# driver_board_v2.net
KiCad netlist of a schematic drawn in EAGLE
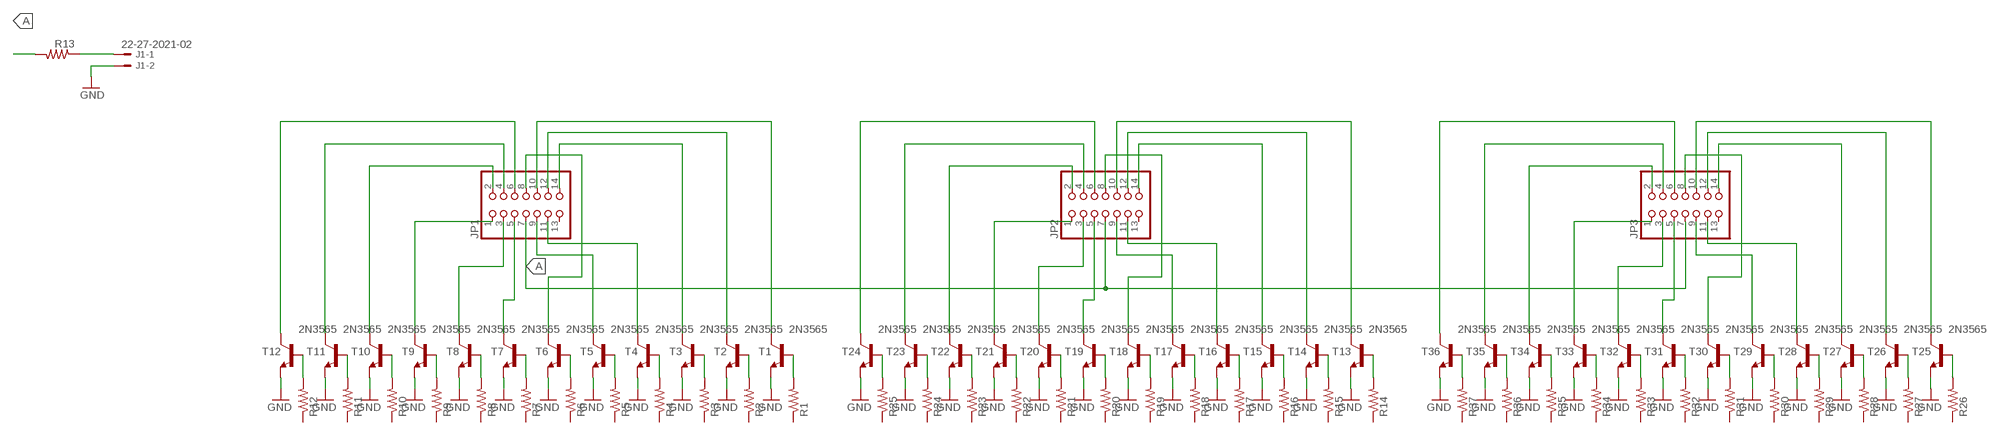
[diagram p0: schematic, sheet 1]

(export (version "E")
  (design (tool "Eeschema 10.0.6"))
  (components
    (comp (ref "J1")
      (value "22-27-2021-02")
      (footprint "eagle-import:6410-02")
      (libsource (lib "eagle-import") (part "22-?-0227-2021"))
    )
    (comp (ref "JP1")
      (value "PINHD-2X7")
      (footprint "eagle-import:2X07")
      (libsource (lib "eagle-import") (part "PINHD-2X7"))
    )
    (comp (ref "JP2")
      (value "PINHD-2X7")
      (footprint "eagle-import:2X07")
      (libsource (lib "eagle-import") (part "PINHD-2X7"))
    )
    (comp (ref "JP3")
      (value "PINHD-2X7")
      (footprint "eagle-import:2X07")
      (libsource (lib "eagle-import") (part "PINHD-2X7"))
    )
    (comp (ref "R1")
      (value "R-US_0204/7")
      (footprint "eagle-import:0204_7")
      (libsource (lib "eagle-import") (part "R-US_0204/7"))
    )
    (comp (ref "R2")
      (value "R-US_0204/7")
      (footprint "eagle-import:0204_7")
      (libsource (lib "eagle-import") (part "R-US_0204/7"))
    )
    (comp (ref "R3")
      (value "R-US_0204/7")
      (footprint "eagle-import:0204_7")
      (libsource (lib "eagle-import") (part "R-US_0204/7"))
    )
    (comp (ref "R4")
      (value "R-US_0204/7")
      (footprint "eagle-import:0204_7")
      (libsource (lib "eagle-import") (part "R-US_0204/7"))
    )
    (comp (ref "R5")
      (value "R-US_0204/7")
      (footprint "eagle-import:0204_7")
      (libsource (lib "eagle-import") (part "R-US_0204/7"))
    )
    (comp (ref "R6")
      (value "R-US_0204/7")
      (footprint "eagle-import:0204_7")
      (libsource (lib "eagle-import") (part "R-US_0204/7"))
    )
    (comp (ref "R7")
      (value "R-US_0204/7")
      (footprint "eagle-import:0204_7")
      (libsource (lib "eagle-import") (part "R-US_0204/7"))
    )
    (comp (ref "R8")
      (value "R-US_0204/7")
      (footprint "eagle-import:0204_7")
      (libsource (lib "eagle-import") (part "R-US_0204/7"))
    )
    (comp (ref "R9")
      (value "R-US_0204/7")
      (footprint "eagle-import:0204_7")
      (libsource (lib "eagle-import") (part "R-US_0204/7"))
    )
    (comp (ref "R10")
      (value "R-US_0204/7")
      (footprint "eagle-import:0204_7")
      (libsource (lib "eagle-import") (part "R-US_0204/7"))
    )
    (comp (ref "R11")
      (value "R-US_0204/7")
      (footprint "eagle-import:0204_7")
      (libsource (lib "eagle-import") (part "R-US_0204/7"))
    )
    (comp (ref "R12")
      (value "R-US_0204/7")
      (footprint "eagle-import:0204_7")
      (libsource (lib "eagle-import") (part "R-US_0204/7"))
    )
    (comp (ref "R13")
      (value "R-US_0204/7")
      (footprint "eagle-import:0204_7")
      (libsource (lib "eagle-import") (part "R-US_0204/7"))
    )
    (comp (ref "R14")
      (value "R-US_0204/7")
      (footprint "eagle-import:0204_7")
      (libsource (lib "eagle-import") (part "R-US_0204/7"))
    )
    (comp (ref "R15")
      (value "R-US_0204/7")
      (footprint "eagle-import:0204_7")
      (libsource (lib "eagle-import") (part "R-US_0204/7"))
    )
    (comp (ref "R16")
      (value "R-US_0204/7")
      (footprint "eagle-import:0204_7")
      (libsource (lib "eagle-import") (part "R-US_0204/7"))
    )
    (comp (ref "R17")
      (value "R-US_0204/7")
      (footprint "eagle-import:0204_7")
      (libsource (lib "eagle-import") (part "R-US_0204/7"))
    )
    (comp (ref "R18")
      (value "R-US_0204/7")
      (footprint "eagle-import:0204_7")
      (libsource (lib "eagle-import") (part "R-US_0204/7"))
    )
    (comp (ref "R19")
      (value "R-US_0204/7")
      (footprint "eagle-import:0204_7")
      (libsource (lib "eagle-import") (part "R-US_0204/7"))
    )
    (comp (ref "R20")
      (value "R-US_0204/7")
      (footprint "eagle-import:0204_7")
      (libsource (lib "eagle-import") (part "R-US_0204/7"))
    )
    (comp (ref "R21")
      (value "R-US_0204/7")
      (footprint "eagle-import:0204_7")
      (libsource (lib "eagle-import") (part "R-US_0204/7"))
    )
    (comp (ref "R22")
      (value "R-US_0204/7")
      (footprint "eagle-import:0204_7")
      (libsource (lib "eagle-import") (part "R-US_0204/7"))
    )
    (comp (ref "R23")
      (value "R-US_0204/7")
      (footprint "eagle-import:0204_7")
      (libsource (lib "eagle-import") (part "R-US_0204/7"))
    )
    (comp (ref "R24")
      (value "R-US_0204/7")
      (footprint "eagle-import:0204_7")
      (libsource (lib "eagle-import") (part "R-US_0204/7"))
    )
    (comp (ref "R25")
      (value "R-US_0204/7")
      (footprint "eagle-import:0204_7")
      (libsource (lib "eagle-import") (part "R-US_0204/7"))
    )
    (comp (ref "R26")
      (value "R-US_0204/7")
      (footprint "eagle-import:0204_7")
      (libsource (lib "eagle-import") (part "R-US_0204/7"))
    )
    (comp (ref "R27")
      (value "R-US_0204/7")
      (footprint "eagle-import:0204_7")
      (libsource (lib "eagle-import") (part "R-US_0204/7"))
    )
    (comp (ref "R28")
      (value "R-US_0204/7")
      (footprint "eagle-import:0204_7")
      (libsource (lib "eagle-import") (part "R-US_0204/7"))
    )
    (comp (ref "R29")
      (value "R-US_0204/7")
      (footprint "eagle-import:0204_7")
      (libsource (lib "eagle-import") (part "R-US_0204/7"))
    )
    (comp (ref "R30")
      (value "R-US_0204/7")
      (footprint "eagle-import:0204_7")
      (libsource (lib "eagle-import") (part "R-US_0204/7"))
    )
    (comp (ref "R31")
      (value "R-US_0204/7")
      (footprint "eagle-import:0204_7")
      (libsource (lib "eagle-import") (part "R-US_0204/7"))
    )
    (comp (ref "R32")
      (value "R-US_0204/7")
      (footprint "eagle-import:0204_7")
      (libsource (lib "eagle-import") (part "R-US_0204/7"))
    )
    (comp (ref "R33")
      (value "R-US_0204/7")
      (footprint "eagle-import:0204_7")
      (libsource (lib "eagle-import") (part "R-US_0204/7"))
    )
    (comp (ref "R34")
      (value "R-US_0204/7")
      (footprint "eagle-import:0204_7")
      (libsource (lib "eagle-import") (part "R-US_0204/7"))
    )
    (comp (ref "R35")
      (value "R-US_0204/7")
      (footprint "eagle-import:0204_7")
      (libsource (lib "eagle-import") (part "R-US_0204/7"))
    )
    (comp (ref "R36")
      (value "R-US_0204/7")
      (footprint "eagle-import:0204_7")
      (libsource (lib "eagle-import") (part "R-US_0204/7"))
    )
    (comp (ref "R37")
      (value "R-US_0204/7")
      (footprint "eagle-import:0204_7")
      (libsource (lib "eagle-import") (part "R-US_0204/7"))
    )
    (comp (ref "T1")
      (value "2N3565")
      (footprint "eagle-import:TO92")
      (libsource (lib "eagle-import") (part "2N3565"))
    )
    (comp (ref "T2")
      (value "2N3565")
      (footprint "eagle-import:TO92")
      (libsource (lib "eagle-import") (part "2N3565"))
    )
    (comp (ref "T3")
      (value "2N3565")
      (footprint "eagle-import:TO92")
      (libsource (lib "eagle-import") (part "2N3565"))
    )
    (comp (ref "T4")
      (value "2N3565")
      (footprint "eagle-import:TO92")
      (libsource (lib "eagle-import") (part "2N3565"))
    )
    (comp (ref "T5")
      (value "2N3565")
      (footprint "eagle-import:TO92")
      (libsource (lib "eagle-import") (part "2N3565"))
    )
    (comp (ref "T6")
      (value "2N3565")
      (footprint "eagle-import:TO92")
      (libsource (lib "eagle-import") (part "2N3565"))
    )
    (comp (ref "T7")
      (value "2N3565")
      (footprint "eagle-import:TO92")
      (libsource (lib "eagle-import") (part "2N3565"))
    )
    (comp (ref "T8")
      (value "2N3565")
      (footprint "eagle-import:TO92")
      (libsource (lib "eagle-import") (part "2N3565"))
    )
    (comp (ref "T9")
      (value "2N3565")
      (footprint "eagle-import:TO92")
      (libsource (lib "eagle-import") (part "2N3565"))
    )
    (comp (ref "T10")
      (value "2N3565")
      (footprint "eagle-import:TO92")
      (libsource (lib "eagle-import") (part "2N3565"))
    )
    (comp (ref "T11")
      (value "2N3565")
      (footprint "eagle-import:TO92")
      (libsource (lib "eagle-import") (part "2N3565"))
    )
    (comp (ref "T12")
      (value "2N3565")
      (footprint "eagle-import:TO92")
      (libsource (lib "eagle-import") (part "2N3565"))
    )
    (comp (ref "T13")
      (value "2N3565")
      (footprint "eagle-import:TO92")
      (libsource (lib "eagle-import") (part "2N3565"))
    )
    (comp (ref "T14")
      (value "2N3565")
      (footprint "eagle-import:TO92")
      (libsource (lib "eagle-import") (part "2N3565"))
    )
    (comp (ref "T15")
      (value "2N3565")
      (footprint "eagle-import:TO92")
      (libsource (lib "eagle-import") (part "2N3565"))
    )
    (comp (ref "T16")
      (value "2N3565")
      (footprint "eagle-import:TO92")
      (libsource (lib "eagle-import") (part "2N3565"))
    )
    (comp (ref "T17")
      (value "2N3565")
      (footprint "eagle-import:TO92")
      (libsource (lib "eagle-import") (part "2N3565"))
    )
    (comp (ref "T18")
      (value "2N3565")
      (footprint "eagle-import:TO92")
      (libsource (lib "eagle-import") (part "2N3565"))
    )
    (comp (ref "T19")
      (value "2N3565")
      (footprint "eagle-import:TO92")
      (libsource (lib "eagle-import") (part "2N3565"))
    )
    (comp (ref "T20")
      (value "2N3565")
      (footprint "eagle-import:TO92")
      (libsource (lib "eagle-import") (part "2N3565"))
    )
    (comp (ref "T21")
      (value "2N3565")
      (footprint "eagle-import:TO92")
      (libsource (lib "eagle-import") (part "2N3565"))
    )
    (comp (ref "T22")
      (value "2N3565")
      (footprint "eagle-import:TO92")
      (libsource (lib "eagle-import") (part "2N3565"))
    )
    (comp (ref "T23")
      (value "2N3565")
      (footprint "eagle-import:TO92")
      (libsource (lib "eagle-import") (part "2N3565"))
    )
    (comp (ref "T24")
      (value "2N3565")
      (footprint "eagle-import:TO92")
      (libsource (lib "eagle-import") (part "2N3565"))
    )
    (comp (ref "T25")
      (value "2N3565")
      (footprint "eagle-import:TO92")
      (libsource (lib "eagle-import") (part "2N3565"))
    )
    (comp (ref "T26")
      (value "2N3565")
      (footprint "eagle-import:TO92")
      (libsource (lib "eagle-import") (part "2N3565"))
    )
    (comp (ref "T27")
      (value "2N3565")
      (footprint "eagle-import:TO92")
      (libsource (lib "eagle-import") (part "2N3565"))
    )
    (comp (ref "T28")
      (value "2N3565")
      (footprint "eagle-import:TO92")
      (libsource (lib "eagle-import") (part "2N3565"))
    )
    (comp (ref "T29")
      (value "2N3565")
      (footprint "eagle-import:TO92")
      (libsource (lib "eagle-import") (part "2N3565"))
    )
    (comp (ref "T30")
      (value "2N3565")
      (footprint "eagle-import:TO92")
      (libsource (lib "eagle-import") (part "2N3565"))
    )
    (comp (ref "T31")
      (value "2N3565")
      (footprint "eagle-import:TO92")
      (libsource (lib "eagle-import") (part "2N3565"))
    )
    (comp (ref "T32")
      (value "2N3565")
      (footprint "eagle-import:TO92")
      (libsource (lib "eagle-import") (part "2N3565"))
    )
    (comp (ref "T33")
      (value "2N3565")
      (footprint "eagle-import:TO92")
      (libsource (lib "eagle-import") (part "2N3565"))
    )
    (comp (ref "T34")
      (value "2N3565")
      (footprint "eagle-import:TO92")
      (libsource (lib "eagle-import") (part "2N3565"))
    )
    (comp (ref "T35")
      (value "2N3565")
      (footprint "eagle-import:TO92")
      (libsource (lib "eagle-import") (part "2N3565"))
    )
    (comp (ref "T36")
      (value "2N3565")
      (footprint "eagle-import:TO92")
      (libsource (lib "eagle-import") (part "2N3565"))
    )
  )
  (nets
    (net (code "1") (name "A") (class "Default")
      (node (ref "JP1") (pin "7") (pinfunction "7_7") (pintype "passive"))
      (node (ref "JP2") (pin "7") (pinfunction "7_7") (pintype "passive"))
      (node (ref "JP3") (pin "7") (pinfunction "7_7") (pintype "passive"))
      (node (ref "R13") (pin "2") (pinfunction "2_2") (pintype "passive"))
    )
    (net (code "2") (name "GND") (class "Default")
      (node (ref "J1") (pin "2") (pinfunction "S_2") (pintype "passive"))
      (node (ref "T1") (pin "3") (pinfunction "E_3") (pintype "passive"))
      (node (ref "T10") (pin "3") (pinfunction "E_3") (pintype "passive"))
      (node (ref "T11") (pin "3") (pinfunction "E_3") (pintype "passive"))
      (node (ref "T12") (pin "3") (pinfunction "E_3") (pintype "passive"))
      (node (ref "T13") (pin "3") (pinfunction "E_3") (pintype "passive"))
      (node (ref "T14") (pin "3") (pinfunction "E_3") (pintype "passive"))
      (node (ref "T15") (pin "3") (pinfunction "E_3") (pintype "passive"))
      (node (ref "T16") (pin "3") (pinfunction "E_3") (pintype "passive"))
      (node (ref "T17") (pin "3") (pinfunction "E_3") (pintype "passive"))
      (node (ref "T18") (pin "3") (pinfunction "E_3") (pintype "passive"))
      (node (ref "T19") (pin "3") (pinfunction "E_3") (pintype "passive"))
      (node (ref "T2") (pin "3") (pinfunction "E_3") (pintype "passive"))
      (node (ref "T20") (pin "3") (pinfunction "E_3") (pintype "passive"))
      (node (ref "T21") (pin "3") (pinfunction "E_3") (pintype "passive"))
      (node (ref "T22") (pin "3") (pinfunction "E_3") (pintype "passive"))
      (node (ref "T23") (pin "3") (pinfunction "E_3") (pintype "passive"))
      (node (ref "T24") (pin "3") (pinfunction "E_3") (pintype "passive"))
      (node (ref "T25") (pin "3") (pinfunction "E_3") (pintype "passive"))
      (node (ref "T26") (pin "3") (pinfunction "E_3") (pintype "passive"))
      (node (ref "T27") (pin "3") (pinfunction "E_3") (pintype "passive"))
      (node (ref "T28") (pin "3") (pinfunction "E_3") (pintype "passive"))
      (node (ref "T29") (pin "3") (pinfunction "E_3") (pintype "passive"))
      (node (ref "T3") (pin "3") (pinfunction "E_3") (pintype "passive"))
      (node (ref "T30") (pin "3") (pinfunction "E_3") (pintype "passive"))
      (node (ref "T31") (pin "3") (pinfunction "E_3") (pintype "passive"))
      (node (ref "T32") (pin "3") (pinfunction "E_3") (pintype "passive"))
      (node (ref "T33") (pin "3") (pinfunction "E_3") (pintype "passive"))
      (node (ref "T34") (pin "3") (pinfunction "E_3") (pintype "passive"))
      (node (ref "T35") (pin "3") (pinfunction "E_3") (pintype "passive"))
      (node (ref "T36") (pin "3") (pinfunction "E_3") (pintype "passive"))
      (node (ref "T4") (pin "3") (pinfunction "E_3") (pintype "passive"))
      (node (ref "T5") (pin "3") (pinfunction "E_3") (pintype "passive"))
      (node (ref "T6") (pin "3") (pinfunction "E_3") (pintype "passive"))
      (node (ref "T7") (pin "3") (pinfunction "E_3") (pintype "passive"))
      (node (ref "T8") (pin "3") (pinfunction "E_3") (pintype "passive"))
      (node (ref "T9") (pin "3") (pinfunction "E_3") (pintype "passive"))
    )
    (net (code "3") (name "Net-(J1A-S)") (class "Default")
      (node (ref "J1") (pin "1") (pinfunction "S_1") (pintype "passive"))
      (node (ref "R13") (pin "1") (pinfunction "1_1") (pintype "passive"))
    )
    (net (code "4") (name "Net-(T1-B)") (class "Default")
      (node (ref "R1") (pin "2") (pinfunction "2_2") (pintype "passive"))
      (node (ref "T1") (pin "2") (pinfunction "B_2") (pintype "passive"))
    )
    (net (code "5") (name "Net-(T1-C)") (class "Default")
      (node (ref "JP1") (pin "10") (pinfunction "10_10") (pintype "passive"))
      (node (ref "T1") (pin "1") (pinfunction "C_1") (pintype "passive"))
    )
    (net (code "6") (name "Net-(T2-B)") (class "Default")
      (node (ref "R2") (pin "2") (pinfunction "2_2") (pintype "passive"))
      (node (ref "T2") (pin "2") (pinfunction "B_2") (pintype "passive"))
    )
    (net (code "7") (name "Net-(T2-C)") (class "Default")
      (node (ref "JP1") (pin "12") (pinfunction "12_12") (pintype "passive"))
      (node (ref "T2") (pin "1") (pinfunction "C_1") (pintype "passive"))
    )
    (net (code "8") (name "Net-(T3-B)") (class "Default")
      (node (ref "R3") (pin "2") (pinfunction "2_2") (pintype "passive"))
      (node (ref "T3") (pin "2") (pinfunction "B_2") (pintype "passive"))
    )
    (net (code "9") (name "Net-(T3-C)") (class "Default")
      (node (ref "JP1") (pin "14") (pinfunction "14_14") (pintype "passive"))
      (node (ref "T3") (pin "1") (pinfunction "C_1") (pintype "passive"))
    )
    (net (code "10") (name "Net-(T4-B)") (class "Default")
      (node (ref "R4") (pin "2") (pinfunction "2_2") (pintype "passive"))
      (node (ref "T4") (pin "2") (pinfunction "B_2") (pintype "passive"))
    )
    (net (code "11") (name "Net-(T4-C)") (class "Default")
      (node (ref "JP1") (pin "11") (pinfunction "11_11") (pintype "passive"))
      (node (ref "T4") (pin "1") (pinfunction "C_1") (pintype "passive"))
    )
    (net (code "12") (name "Net-(T5-B)") (class "Default")
      (node (ref "R5") (pin "2") (pinfunction "2_2") (pintype "passive"))
      (node (ref "T5") (pin "2") (pinfunction "B_2") (pintype "passive"))
    )
    (net (code "13") (name "Net-(T5-C)") (class "Default")
      (node (ref "JP1") (pin "9") (pinfunction "9_9") (pintype "passive"))
      (node (ref "T5") (pin "1") (pinfunction "C_1") (pintype "passive"))
    )
    (net (code "14") (name "Net-(T6-B)") (class "Default")
      (node (ref "R6") (pin "2") (pinfunction "2_2") (pintype "passive"))
      (node (ref "T6") (pin "2") (pinfunction "B_2") (pintype "passive"))
    )
    (net (code "15") (name "Net-(T6-C)") (class "Default")
      (node (ref "JP1") (pin "8") (pinfunction "8_8") (pintype "passive"))
      (node (ref "T6") (pin "1") (pinfunction "C_1") (pintype "passive"))
    )
    (net (code "16") (name "Net-(T7-B)") (class "Default")
      (node (ref "R7") (pin "2") (pinfunction "2_2") (pintype "passive"))
      (node (ref "T7") (pin "2") (pinfunction "B_2") (pintype "passive"))
    )
    (net (code "17") (name "Net-(T7-C)") (class "Default")
      (node (ref "JP1") (pin "5") (pinfunction "5_5") (pintype "passive"))
      (node (ref "T7") (pin "1") (pinfunction "C_1") (pintype "passive"))
    )
    (net (code "18") (name "Net-(T8-B)") (class "Default")
      (node (ref "R8") (pin "2") (pinfunction "2_2") (pintype "passive"))
      (node (ref "T8") (pin "2") (pinfunction "B_2") (pintype "passive"))
    )
    (net (code "19") (name "Net-(T8-C)") (class "Default")
      (node (ref "JP1") (pin "3") (pinfunction "3_3") (pintype "passive"))
      (node (ref "T8") (pin "1") (pinfunction "C_1") (pintype "passive"))
    )
    (net (code "20") (name "Net-(T9-B)") (class "Default")
      (node (ref "R9") (pin "2") (pinfunction "2_2") (pintype "passive"))
      (node (ref "T9") (pin "2") (pinfunction "B_2") (pintype "passive"))
    )
    (net (code "21") (name "Net-(T9-C)") (class "Default")
      (node (ref "JP1") (pin "1") (pinfunction "1_1") (pintype "passive"))
      (node (ref "T9") (pin "1") (pinfunction "C_1") (pintype "passive"))
    )
    (net (code "22") (name "Net-(T10-B)") (class "Default")
      (node (ref "R10") (pin "2") (pinfunction "2_2") (pintype "passive"))
      (node (ref "T10") (pin "2") (pinfunction "B_2") (pintype "passive"))
    )
    (net (code "23") (name "Net-(T10-C)") (class "Default")
      (node (ref "JP1") (pin "2") (pinfunction "2_2") (pintype "passive"))
      (node (ref "T10") (pin "1") (pinfunction "C_1") (pintype "passive"))
    )
    (net (code "24") (name "Net-(T11-B)") (class "Default")
      (node (ref "R11") (pin "2") (pinfunction "2_2") (pintype "passive"))
      (node (ref "T11") (pin "2") (pinfunction "B_2") (pintype "passive"))
    )
    (net (code "25") (name "Net-(T11-C)") (class "Default")
      (node (ref "JP1") (pin "4") (pinfunction "4_4") (pintype "passive"))
      (node (ref "T11") (pin "1") (pinfunction "C_1") (pintype "passive"))
    )
    (net (code "26") (name "Net-(T12-B)") (class "Default")
      (node (ref "R12") (pin "2") (pinfunction "2_2") (pintype "passive"))
      (node (ref "T12") (pin "2") (pinfunction "B_2") (pintype "passive"))
    )
    (net (code "27") (name "Net-(T12-C)") (class "Default")
      (node (ref "JP1") (pin "6") (pinfunction "6_6") (pintype "passive"))
      (node (ref "T12") (pin "1") (pinfunction "C_1") (pintype "passive"))
    )
    (net (code "28") (name "Net-(T13-B)") (class "Default")
      (node (ref "R14") (pin "2") (pinfunction "2_2") (pintype "passive"))
      (node (ref "T13") (pin "2") (pinfunction "B_2") (pintype "passive"))
    )
    (net (code "29") (name "Net-(T13-C)") (class "Default")
      (node (ref "JP2") (pin "10") (pinfunction "10_10") (pintype "passive"))
      (node (ref "T13") (pin "1") (pinfunction "C_1") (pintype "passive"))
    )
    (net (code "30") (name "Net-(T14-B)") (class "Default")
      (node (ref "R15") (pin "2") (pinfunction "2_2") (pintype "passive"))
      (node (ref "T14") (pin "2") (pinfunction "B_2") (pintype "passive"))
    )
    (net (code "31") (name "Net-(T14-C)") (class "Default")
      (node (ref "JP2") (pin "12") (pinfunction "12_12") (pintype "passive"))
      (node (ref "T14") (pin "1") (pinfunction "C_1") (pintype "passive"))
    )
    (net (code "32") (name "Net-(T15-B)") (class "Default")
      (node (ref "R16") (pin "2") (pinfunction "2_2") (pintype "passive"))
      (node (ref "T15") (pin "2") (pinfunction "B_2") (pintype "passive"))
    )
    (net (code "33") (name "Net-(T15-C)") (class "Default")
      (node (ref "JP2") (pin "14") (pinfunction "14_14") (pintype "passive"))
      (node (ref "T15") (pin "1") (pinfunction "C_1") (pintype "passive"))
    )
    (net (code "34") (name "Net-(T16-B)") (class "Default")
      (node (ref "R17") (pin "2") (pinfunction "2_2") (pintype "passive"))
      (node (ref "T16") (pin "2") (pinfunction "B_2") (pintype "passive"))
    )
    (net (code "35") (name "Net-(T16-C)") (class "Default")
      (node (ref "JP2") (pin "11") (pinfunction "11_11") (pintype "passive"))
      (node (ref "T16") (pin "1") (pinfunction "C_1") (pintype "passive"))
    )
    (net (code "36") (name "Net-(T17-B)") (class "Default")
      (node (ref "R18") (pin "2") (pinfunction "2_2") (pintype "passive"))
      (node (ref "T17") (pin "2") (pinfunction "B_2") (pintype "passive"))
    )
    (net (code "37") (name "Net-(T17-C)") (class "Default")
      (node (ref "JP2") (pin "9") (pinfunction "9_9") (pintype "passive"))
      (node (ref "T17") (pin "1") (pinfunction "C_1") (pintype "passive"))
    )
    (net (code "38") (name "Net-(T18-B)") (class "Default")
      (node (ref "R19") (pin "2") (pinfunction "2_2") (pintype "passive"))
      (node (ref "T18") (pin "2") (pinfunction "B_2") (pintype "passive"))
    )
    (net (code "39") (name "Net-(T18-C)") (class "Default")
      (node (ref "JP2") (pin "8") (pinfunction "8_8") (pintype "passive"))
      (node (ref "T18") (pin "1") (pinfunction "C_1") (pintype "passive"))
    )
    (net (code "40") (name "Net-(T19-B)") (class "Default")
      (node (ref "R20") (pin "2") (pinfunction "2_2") (pintype "passive"))
      (node (ref "T19") (pin "2") (pinfunction "B_2") (pintype "passive"))
    )
    (net (code "41") (name "Net-(T19-C)") (class "Default")
      (node (ref "JP2") (pin "5") (pinfunction "5_5") (pintype "passive"))
      (node (ref "T19") (pin "1") (pinfunction "C_1") (pintype "passive"))
    )
    (net (code "42") (name "Net-(T20-B)") (class "Default")
      (node (ref "R21") (pin "2") (pinfunction "2_2") (pintype "passive"))
      (node (ref "T20") (pin "2") (pinfunction "B_2") (pintype "passive"))
    )
    (net (code "43") (name "Net-(T20-C)") (class "Default")
      (node (ref "JP2") (pin "3") (pinfunction "3_3") (pintype "passive"))
      (node (ref "T20") (pin "1") (pinfunction "C_1") (pintype "passive"))
    )
    (net (code "44") (name "Net-(T21-B)") (class "Default")
      (node (ref "R22") (pin "2") (pinfunction "2_2") (pintype "passive"))
      (node (ref "T21") (pin "2") (pinfunction "B_2") (pintype "passive"))
    )
    (net (code "45") (name "Net-(T21-C)") (class "Default")
      (node (ref "JP2") (pin "1") (pinfunction "1_1") (pintype "passive"))
      (node (ref "T21") (pin "1") (pinfunction "C_1") (pintype "passive"))
    )
    (net (code "46") (name "Net-(T22-B)") (class "Default")
      (node (ref "R23") (pin "2") (pinfunction "2_2") (pintype "passive"))
      (node (ref "T22") (pin "2") (pinfunction "B_2") (pintype "passive"))
    )
    (net (code "47") (name "Net-(T22-C)") (class "Default")
      (node (ref "JP2") (pin "2") (pinfunction "2_2") (pintype "passive"))
      (node (ref "T22") (pin "1") (pinfunction "C_1") (pintype "passive"))
    )
    (net (code "48") (name "Net-(T23-B)") (class "Default")
      (node (ref "R24") (pin "2") (pinfunction "2_2") (pintype "passive"))
      (node (ref "T23") (pin "2") (pinfunction "B_2") (pintype "passive"))
    )
    (net (code "49") (name "Net-(T23-C)") (class "Default")
      (node (ref "JP2") (pin "4") (pinfunction "4_4") (pintype "passive"))
      (node (ref "T23") (pin "1") (pinfunction "C_1") (pintype "passive"))
    )
    (net (code "50") (name "Net-(T24-B)") (class "Default")
      (node (ref "R25") (pin "2") (pinfunction "2_2") (pintype "passive"))
      (node (ref "T24") (pin "2") (pinfunction "B_2") (pintype "passive"))
    )
    (net (code "51") (name "Net-(T24-C)") (class "Default")
      (node (ref "JP2") (pin "6") (pinfunction "6_6") (pintype "passive"))
      (node (ref "T24") (pin "1") (pinfunction "C_1") (pintype "passive"))
    )
    (net (code "52") (name "Net-(T25-B)") (class "Default")
      (node (ref "R26") (pin "2") (pinfunction "2_2") (pintype "passive"))
      (node (ref "T25") (pin "2") (pinfunction "B_2") (pintype "passive"))
    )
    (net (code "53") (name "Net-(T25-C)") (class "Default")
      (node (ref "JP3") (pin "10") (pinfunction "10_10") (pintype "passive"))
      (node (ref "T25") (pin "1") (pinfunction "C_1") (pintype "passive"))
    )
    (net (code "54") (name "Net-(T26-B)") (class "Default")
      (node (ref "R27") (pin "2") (pinfunction "2_2") (pintype "passive"))
      (node (ref "T26") (pin "2") (pinfunction "B_2") (pintype "passive"))
    )
    (net (code "55") (name "Net-(T26-C)") (class "Default")
      (node (ref "JP3") (pin "12") (pinfunction "12_12") (pintype "passive"))
      (node (ref "T26") (pin "1") (pinfunction "C_1") (pintype "passive"))
    )
    (net (code "56") (name "Net-(T27-B)") (class "Default")
      (node (ref "R28") (pin "2") (pinfunction "2_2") (pintype "passive"))
      (node (ref "T27") (pin "2") (pinfunction "B_2") (pintype "passive"))
    )
    (net (code "57") (name "Net-(T27-C)") (class "Default")
      (node (ref "JP3") (pin "14") (pinfunction "14_14") (pintype "passive"))
      (node (ref "T27") (pin "1") (pinfunction "C_1") (pintype "passive"))
    )
    (net (code "58") (name "Net-(T28-B)") (class "Default")
      (node (ref "R29") (pin "2") (pinfunction "2_2") (pintype "passive"))
      (node (ref "T28") (pin "2") (pinfunction "B_2") (pintype "passive"))
    )
    (net (code "59") (name "Net-(T28-C)") (class "Default")
      (node (ref "JP3") (pin "11") (pinfunction "11_11") (pintype "passive"))
      (node (ref "T28") (pin "1") (pinfunction "C_1") (pintype "passive"))
    )
    (net (code "60") (name "Net-(T29-B)") (class "Default")
      (node (ref "R30") (pin "2") (pinfunction "2_2") (pintype "passive"))
      (node (ref "T29") (pin "2") (pinfunction "B_2") (pintype "passive"))
    )
    (net (code "61") (name "Net-(T29-C)") (class "Default")
      (node (ref "JP3") (pin "9") (pinfunction "9_9") (pintype "passive"))
      (node (ref "T29") (pin "1") (pinfunction "C_1") (pintype "passive"))
    )
    (net (code "62") (name "Net-(T30-B)") (class "Default")
      (node (ref "R31") (pin "2") (pinfunction "2_2") (pintype "passive"))
      (node (ref "T30") (pin "2") (pinfunction "B_2") (pintype "passive"))
    )
    (net (code "63") (name "Net-(T30-C)") (class "Default")
      (node (ref "JP3") (pin "8") (pinfunction "8_8") (pintype "passive"))
      (node (ref "T30") (pin "1") (pinfunction "C_1") (pintype "passive"))
    )
    (net (code "64") (name "Net-(T31-B)") (class "Default")
      (node (ref "R32") (pin "2") (pinfunction "2_2") (pintype "passive"))
      (node (ref "T31") (pin "2") (pinfunction "B_2") (pintype "passive"))
    )
    (net (code "65") (name "Net-(T31-C)") (class "Default")
      (node (ref "JP3") (pin "5") (pinfunction "5_5") (pintype "passive"))
      (node (ref "T31") (pin "1") (pinfunction "C_1") (pintype "passive"))
    )
    (net (code "66") (name "Net-(T32-B)") (class "Default")
      (node (ref "R33") (pin "2") (pinfunction "2_2") (pintype "passive"))
      (node (ref "T32") (pin "2") (pinfunction "B_2") (pintype "passive"))
    )
    (net (code "67") (name "Net-(T32-C)") (class "Default")
      (node (ref "JP3") (pin "3") (pinfunction "3_3") (pintype "passive"))
      (node (ref "T32") (pin "1") (pinfunction "C_1") (pintype "passive"))
    )
    (net (code "68") (name "Net-(T33-B)") (class "Default")
      (node (ref "R34") (pin "2") (pinfunction "2_2") (pintype "passive"))
      (node (ref "T33") (pin "2") (pinfunction "B_2") (pintype "passive"))
    )
    (net (code "69") (name "Net-(T33-C)") (class "Default")
      (node (ref "JP3") (pin "1") (pinfunction "1_1") (pintype "passive"))
      (node (ref "T33") (pin "1") (pinfunction "C_1") (pintype "passive"))
    )
    (net (code "70") (name "Net-(T34-B)") (class "Default")
      (node (ref "R35") (pin "2") (pinfunction "2_2") (pintype "passive"))
      (node (ref "T34") (pin "2") (pinfunction "B_2") (pintype "passive"))
    )
    (net (code "71") (name "Net-(T34-C)") (class "Default")
      (node (ref "JP3") (pin "2") (pinfunction "2_2") (pintype "passive"))
      (node (ref "T34") (pin "1") (pinfunction "C_1") (pintype "passive"))
    )
    (net (code "72") (name "Net-(T35-B)") (class "Default")
      (node (ref "R36") (pin "2") (pinfunction "2_2") (pintype "passive"))
      (node (ref "T35") (pin "2") (pinfunction "B_2") (pintype "passive"))
    )
    (net (code "73") (name "Net-(T35-C)") (class "Default")
      (node (ref "JP3") (pin "4") (pinfunction "4_4") (pintype "passive"))
      (node (ref "T35") (pin "1") (pinfunction "C_1") (pintype "passive"))
    )
    (net (code "74") (name "Net-(T36-B)") (class "Default")
      (node (ref "R37") (pin "2") (pinfunction "2_2") (pintype "passive"))
      (node (ref "T36") (pin "2") (pinfunction "B_2") (pintype "passive"))
    )
    (net (code "75") (name "Net-(T36-C)") (class "Default")
      (node (ref "JP3") (pin "6") (pinfunction "6_6") (pintype "passive"))
      (node (ref "T36") (pin "1") (pinfunction "C_1") (pintype "passive"))
    )
    (net (code "76") (name "unconnected-(JP1-Pad13)") (class "Default")
      (node (ref "JP1") (pin "13") (pinfunction "13_13") (pintype "passive"))
    )
    (net (code "77") (name "unconnected-(JP2-Pad13)") (class "Default")
      (node (ref "JP2") (pin "13") (pinfunction "13_13") (pintype "passive"))
    )
    (net (code "78") (name "unconnected-(JP3-Pad13)") (class "Default")
      (node (ref "JP3") (pin "13") (pinfunction "13_13") (pintype "passive"))
    )
    (net (code "79") (name "unconnected-(R1-Pad1)") (class "Default")
      (node (ref "R1") (pin "1") (pinfunction "1_1") (pintype "passive"))
    )
    (net (code "80") (name "unconnected-(R2-Pad1)") (class "Default")
      (node (ref "R2") (pin "1") (pinfunction "1_1") (pintype "passive"))
    )
    (net (code "81") (name "unconnected-(R3-Pad1)") (class "Default")
      (node (ref "R3") (pin "1") (pinfunction "1_1") (pintype "passive"))
    )
    (net (code "82") (name "unconnected-(R4-Pad1)") (class "Default")
      (node (ref "R4") (pin "1") (pinfunction "1_1") (pintype "passive"))
    )
    (net (code "83") (name "unconnected-(R5-Pad1)") (class "Default")
      (node (ref "R5") (pin "1") (pinfunction "1_1") (pintype "passive"))
    )
    (net (code "84") (name "unconnected-(R6-Pad1)") (class "Default")
      (node (ref "R6") (pin "1") (pinfunction "1_1") (pintype "passive"))
    )
    (net (code "85") (name "unconnected-(R7-Pad1)") (class "Default")
      (node (ref "R7") (pin "1") (pinfunction "1_1") (pintype "passive"))
    )
    (net (code "86") (name "unconnected-(R8-Pad1)") (class "Default")
      (node (ref "R8") (pin "1") (pinfunction "1_1") (pintype "passive"))
    )
    (net (code "87") (name "unconnected-(R9-Pad1)") (class "Default")
      (node (ref "R9") (pin "1") (pinfunction "1_1") (pintype "passive"))
    )
    (net (code "88") (name "unconnected-(R10-Pad1)") (class "Default")
      (node (ref "R10") (pin "1") (pinfunction "1_1") (pintype "passive"))
    )
    (net (code "89") (name "unconnected-(R11-Pad1)") (class "Default")
      (node (ref "R11") (pin "1") (pinfunction "1_1") (pintype "passive"))
    )
    (net (code "90") (name "unconnected-(R12-Pad1)") (class "Default")
      (node (ref "R12") (pin "1") (pinfunction "1_1") (pintype "passive"))
    )
    (net (code "91") (name "unconnected-(R14-Pad1)") (class "Default")
      (node (ref "R14") (pin "1") (pinfunction "1_1") (pintype "passive"))
    )
    (net (code "92") (name "unconnected-(R15-Pad1)") (class "Default")
      (node (ref "R15") (pin "1") (pinfunction "1_1") (pintype "passive"))
    )
    (net (code "93") (name "unconnected-(R16-Pad1)") (class "Default")
      (node (ref "R16") (pin "1") (pinfunction "1_1") (pintype "passive"))
    )
    (net (code "94") (name "unconnected-(R17-Pad1)") (class "Default")
      (node (ref "R17") (pin "1") (pinfunction "1_1") (pintype "passive"))
    )
    (net (code "95") (name "unconnected-(R18-Pad1)") (class "Default")
      (node (ref "R18") (pin "1") (pinfunction "1_1") (pintype "passive"))
    )
    (net (code "96") (name "unconnected-(R19-Pad1)") (class "Default")
      (node (ref "R19") (pin "1") (pinfunction "1_1") (pintype "passive"))
    )
    (net (code "97") (name "unconnected-(R20-Pad1)") (class "Default")
      (node (ref "R20") (pin "1") (pinfunction "1_1") (pintype "passive"))
    )
    (net (code "98") (name "unconnected-(R21-Pad1)") (class "Default")
      (node (ref "R21") (pin "1") (pinfunction "1_1") (pintype "passive"))
    )
    (net (code "99") (name "unconnected-(R22-Pad1)") (class "Default")
      (node (ref "R22") (pin "1") (pinfunction "1_1") (pintype "passive"))
    )
    (net (code "100") (name "unconnected-(R23-Pad1)") (class "Default")
      (node (ref "R23") (pin "1") (pinfunction "1_1") (pintype "passive"))
    )
    (net (code "101") (name "unconnected-(R24-Pad1)") (class "Default")
      (node (ref "R24") (pin "1") (pinfunction "1_1") (pintype "passive"))
    )
    (net (code "102") (name "unconnected-(R25-Pad1)") (class "Default")
      (node (ref "R25") (pin "1") (pinfunction "1_1") (pintype "passive"))
    )
    (net (code "103") (name "unconnected-(R26-Pad1)") (class "Default")
      (node (ref "R26") (pin "1") (pinfunction "1_1") (pintype "passive"))
    )
    (net (code "104") (name "unconnected-(R27-Pad1)") (class "Default")
      (node (ref "R27") (pin "1") (pinfunction "1_1") (pintype "passive"))
    )
    (net (code "105") (name "unconnected-(R28-Pad1)") (class "Default")
      (node (ref "R28") (pin "1") (pinfunction "1_1") (pintype "passive"))
    )
    (net (code "106") (name "unconnected-(R29-Pad1)") (class "Default")
      (node (ref "R29") (pin "1") (pinfunction "1_1") (pintype "passive"))
    )
    (net (code "107") (name "unconnected-(R30-Pad1)") (class "Default")
      (node (ref "R30") (pin "1") (pinfunction "1_1") (pintype "passive"))
    )
    (net (code "108") (name "unconnected-(R31-Pad1)") (class "Default")
      (node (ref "R31") (pin "1") (pinfunction "1_1") (pintype "passive"))
    )
    (net (code "109") (name "unconnected-(R32-Pad1)") (class "Default")
      (node (ref "R32") (pin "1") (pinfunction "1_1") (pintype "passive"))
    )
    (net (code "110") (name "unconnected-(R33-Pad1)") (class "Default")
      (node (ref "R33") (pin "1") (pinfunction "1_1") (pintype "passive"))
    )
    (net (code "111") (name "unconnected-(R34-Pad1)") (class "Default")
      (node (ref "R34") (pin "1") (pinfunction "1_1") (pintype "passive"))
    )
    (net (code "112") (name "unconnected-(R35-Pad1)") (class "Default")
      (node (ref "R35") (pin "1") (pinfunction "1_1") (pintype "passive"))
    )
    (net (code "113") (name "unconnected-(R36-Pad1)") (class "Default")
      (node (ref "R36") (pin "1") (pinfunction "1_1") (pintype "passive"))
    )
    (net (code "114") (name "unconnected-(R37-Pad1)") (class "Default")
      (node (ref "R37") (pin "1") (pinfunction "1_1") (pintype "passive"))
    )
  )
)
